# Heating_Controller.net
KiCad netlist of a schematic drawn in EAGLE
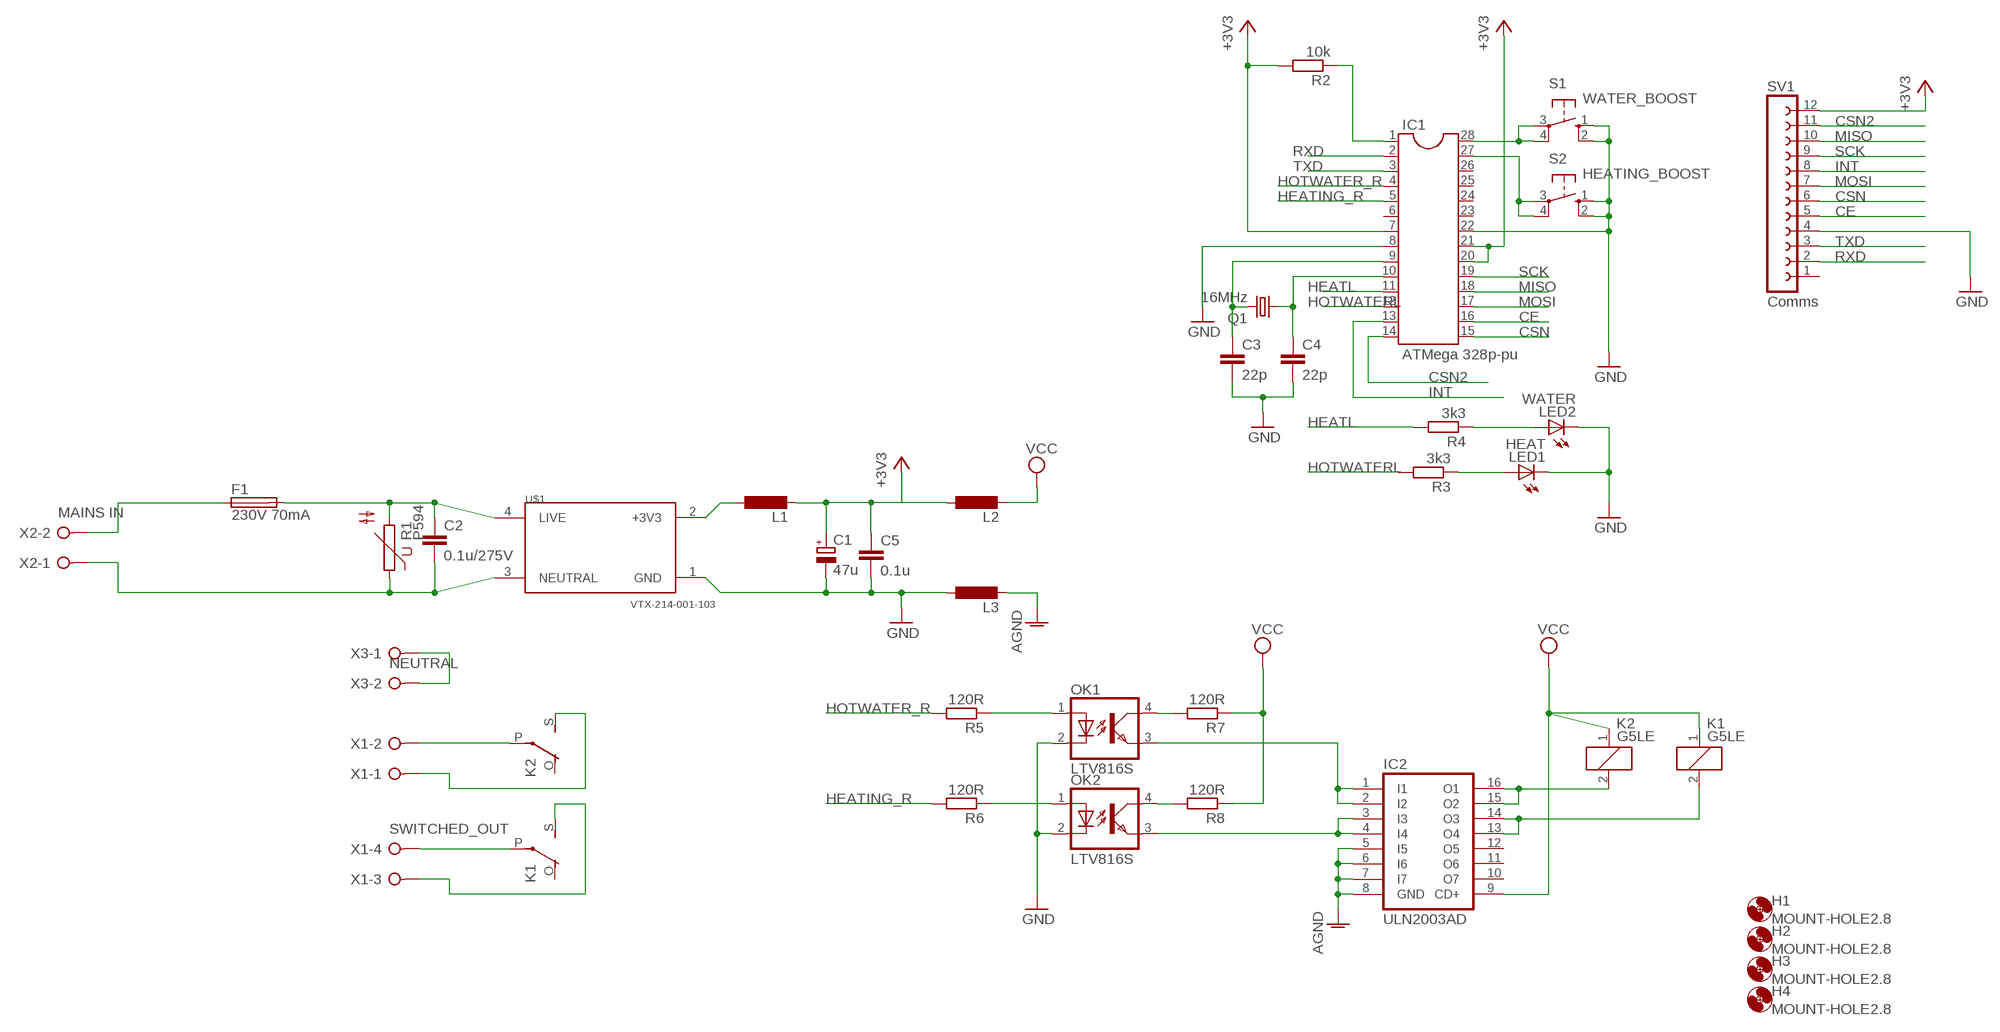
[diagram p0: schematic, sheet 1]

(export (version "E")
  (design (tool "Eeschema 10.0.6"))
  (components
    (comp (ref "C1")
      (value "47u")
      (footprint "eagle-import:E2,5-7")
      (libsource (lib "eagle-import") (part "CPOL-EUE2.5-7"))
    )
    (comp (ref "C2")
      (value "0.1u/275V")
      (footprint "eagle-import:C15B5")
      (libsource (lib "eagle-import") (part "C15/5"))
    )
    (comp (ref "C3")
      (value "22p")
      (footprint "eagle-import:C1206K")
      (libsource (lib "eagle-import") (part "C-EUC1206K"))
    )
    (comp (ref "C4")
      (value "22p")
      (footprint "eagle-import:C1206K")
      (libsource (lib "eagle-import") (part "C-EUC1206K"))
    )
    (comp (ref "C5")
      (value "0.1u")
      (footprint "eagle-import:C1206K")
      (libsource (lib "eagle-import") (part "C-EUC1206K"))
    )
    (comp (ref "F1")
      (value "230V 70mA")
      (footprint "eagle-import:SH22,5A")
      (fields (field (name "MPN") "0031.7701.11"))
      (libsource (lib "eagle-import") (part "SH22,5A"))
    )
    (comp (ref "H1")
      (value "MOUNT-HOLE2.8")
      (footprint "eagle-import:2,8")
      (libsource (lib "eagle-import") (part "MOUNT-HOLE2.8"))
    )
    (comp (ref "H2")
      (value "MOUNT-HOLE2.8")
      (footprint "eagle-import:2,8")
      (libsource (lib "eagle-import") (part "MOUNT-HOLE2.8"))
    )
    (comp (ref "H3")
      (value "MOUNT-HOLE2.8")
      (footprint "eagle-import:2,8")
      (libsource (lib "eagle-import") (part "MOUNT-HOLE2.8"))
    )
    (comp (ref "H4")
      (value "MOUNT-HOLE2.8")
      (footprint "eagle-import:2,8")
      (libsource (lib "eagle-import") (part "MOUNT-HOLE2.8"))
    )
    (comp (ref "IC1")
      (value "ATMega 328p-pu")
      (footprint "eagle-import:DIL28-3")
      (libsource (lib "eagle-import") (part "DIL28-3"))
    )
    (comp (ref "IC2")
      (value "ULN2003AD")
      (footprint "eagle-import:SO16")
      (libsource (lib "eagle-import") (part "ULN2003AD"))
    )
    (comp (ref "K1")
      (value "G5LE")
      (footprint "eagle-import:G5LE")
      (libsource (lib "eagle-import") (part "G5LE"))
    )
    (comp (ref "K2")
      (value "G5LE")
      (footprint "eagle-import:G5LE")
      (libsource (lib "eagle-import") (part "G5LE"))
    )
    (comp (ref "L1")
      (value "L-EUL3230M")
      (footprint "eagle-import:L3230M")
      (libsource (lib "eagle-import") (part "L-EUL3230M"))
    )
    (comp (ref "L2")
      (value "L-EUL3230M")
      (footprint "eagle-import:L3230M")
      (libsource (lib "eagle-import") (part "L-EUL3230M"))
    )
    (comp (ref "L3")
      (value "L-EUL3230M")
      (footprint "eagle-import:L3230M")
      (libsource (lib "eagle-import") (part "L-EUL3230M"))
    )
    (comp (ref "LED1")
      (value "HEAT")
      (footprint "eagle-import:LED5MM")
      (libsource (lib "eagle-import") (part "LED5MM"))
    )
    (comp (ref "LED2")
      (value "WATER")
      (footprint "eagle-import:LED5MM")
      (libsource (lib "eagle-import") (part "LED5MM"))
    )
    (comp (ref "OK1")
      (value "LTV816S")
      (footprint "eagle-import:DIL4-SMD")
      (libsource (lib "eagle-import") (part "LTV816S"))
    )
    (comp (ref "OK2")
      (value "LTV816S")
      (footprint "eagle-import:DIL4-SMD")
      (libsource (lib "eagle-import") (part "LTV816S"))
    )
    (comp (ref "Q1")
      (value "16MHz")
      (footprint "eagle-import:HC49_S")
      (libsource (lib "eagle-import") (part "CRYSTALHC49S"))
    )
    (comp (ref "R1")
      (value "P594")
      (footprint "eagle-import:P594")
      (libsource (lib "eagle-import") (part "P594"))
    )
    (comp (ref "R2")
      (value "10k")
      (footprint "eagle-import:R1206")
      (libsource (lib "eagle-import") (part "R-EU_R1206"))
    )
    (comp (ref "R3")
      (value "3k3")
      (footprint "eagle-import:R1206")
      (libsource (lib "eagle-import") (part "R-EU_R1206"))
    )
    (comp (ref "R4")
      (value "3k3")
      (footprint "eagle-import:R1206")
      (libsource (lib "eagle-import") (part "R-EU_R1206"))
    )
    (comp (ref "R5")
      (value "120R")
      (footprint "eagle-import:R1206")
      (libsource (lib "eagle-import") (part "R-EU_R1206"))
    )
    (comp (ref "R6")
      (value "120R")
      (footprint "eagle-import:R1206")
      (libsource (lib "eagle-import") (part "R-EU_R1206"))
    )
    (comp (ref "R7")
      (value "120R")
      (footprint "eagle-import:R1206")
      (libsource (lib "eagle-import") (part "R-EU_R1206"))
    )
    (comp (ref "R8")
      (value "120R")
      (footprint "eagle-import:R1206")
      (libsource (lib "eagle-import") (part "R-EU_R1206"))
    )
    (comp (ref "S1")
      (value "WATER_BOOST")
      (footprint "eagle-import:B3F-40XX")
      (fields (field (name "MF") "OMRON COMPONENTS USA") (field (name "MPN") "B3F-4000"))
      (libsource (lib "eagle-import") (part "40-XX"))
    )
    (comp (ref "S2")
      (value "HEATING_BOOST")
      (footprint "eagle-import:B3F-40XX")
      (fields (field (name "MF") "OMRON COMPONENTS USA") (field (name "MPN") "B3F-4000"))
      (libsource (lib "eagle-import") (part "40-XX"))
    )
    (comp (ref "SV1")
      (value "Comms")
      (footprint "eagle-import:FE12W")
      (libsource (lib "eagle-import") (part "FE12W"))
    )
    (comp (ref "U$1")
      (value "VTX-214-001-103")
      (footprint "eagle-import:VTX214001103")
      (libsource (lib "eagle-import") (part "VTX-214-001-103"))
    )
    (comp (ref "X1")
      (value "SWITCHED_OUT")
      (footprint "eagle-import:W237-4P")
      (libsource (lib "eagle-import") (part "W237-04P"))
    )
    (comp (ref "X2")
      (value "MAINS IN")
      (footprint "eagle-import:W237-132")
      (libsource (lib "eagle-import") (part "W237-02P"))
    )
    (comp (ref "X3")
      (value "NEUTRAL")
      (footprint "eagle-import:W237-132")
      (libsource (lib "eagle-import") (part "W237-02P"))
    )
  )
  (nets
    (net (code "1") (name "+3V3") (class "Default")
      (node (ref "C1") (pin "+") (pinfunction "+_+") (pintype "passive"))
      (node (ref "C5") (pin "1") (pinfunction "1_1") (pintype "passive"))
      (node (ref "IC1") (pin "20") (pinfunction "20_20") (pintype "passive"))
      (node (ref "IC1") (pin "21") (pinfunction "21_21") (pintype "passive"))
      (node (ref "IC1") (pin "7") (pinfunction "7_7") (pintype "passive"))
      (node (ref "L1") (pin "2") (pinfunction "2_2") (pintype "passive"))
      (node (ref "L2") (pin "1") (pinfunction "1_1") (pintype "passive"))
      (node (ref "R2") (pin "2") (pinfunction "2_2") (pintype "passive"))
      (node (ref "SV1") (pin "12") (pinfunction "12_12") (pintype "passive"))
    )
    (net (code "2") (name "/CE") (class "Default")
      (node (ref "IC1") (pin "16") (pinfunction "16_16") (pintype "passive"))
      (node (ref "SV1") (pin "5") (pinfunction "5_5") (pintype "passive"))
    )
    (net (code "3") (name "/CSN") (class "Default")
      (node (ref "IC1") (pin "15") (pinfunction "15_15") (pintype "passive"))
      (node (ref "SV1") (pin "6") (pinfunction "6_6") (pintype "passive"))
    )
    (net (code "4") (name "/CSN2") (class "Default")
      (node (ref "IC1") (pin "14") (pinfunction "14_14") (pintype "passive"))
      (node (ref "SV1") (pin "11") (pinfunction "11_11") (pintype "passive"))
    )
    (net (code "5") (name "/HEATING_R") (class "Default")
      (node (ref "IC1") (pin "5") (pinfunction "5_5") (pintype "passive"))
      (node (ref "R6") (pin "2") (pinfunction "2_2") (pintype "passive"))
    )
    (net (code "6") (name "/HEATL") (class "Default")
      (node (ref "IC1") (pin "11") (pinfunction "11_11") (pintype "passive"))
      (node (ref "R4") (pin "2") (pinfunction "2_2") (pintype "passive"))
    )
    (net (code "7") (name "/HOTWATERL") (class "Default")
      (node (ref "IC1") (pin "12") (pinfunction "12_12") (pintype "passive"))
      (node (ref "R3") (pin "2") (pinfunction "2_2") (pintype "passive"))
    )
    (net (code "8") (name "/HOTWATER_R") (class "Default")
      (node (ref "IC1") (pin "4") (pinfunction "4_4") (pintype "passive"))
      (node (ref "R5") (pin "2") (pinfunction "2_2") (pintype "passive"))
    )
    (net (code "9") (name "/INT") (class "Default")
      (node (ref "IC1") (pin "13") (pinfunction "13_13") (pintype "passive"))
      (node (ref "SV1") (pin "8") (pinfunction "8_8") (pintype "passive"))
    )
    (net (code "10") (name "/MISO") (class "Default")
      (node (ref "IC1") (pin "18") (pinfunction "18_18") (pintype "passive"))
      (node (ref "SV1") (pin "10") (pinfunction "10_10") (pintype "passive"))
    )
    (net (code "11") (name "/MOSI") (class "Default")
      (node (ref "IC1") (pin "17") (pinfunction "17_17") (pintype "passive"))
      (node (ref "SV1") (pin "7") (pinfunction "7_7") (pintype "passive"))
    )
    (net (code "12") (name "/RXD") (class "Default")
      (node (ref "IC1") (pin "2") (pinfunction "2_2") (pintype "passive"))
      (node (ref "SV1") (pin "2") (pinfunction "2_2") (pintype "passive"))
    )
    (net (code "13") (name "/SCK") (class "Default")
      (node (ref "IC1") (pin "19") (pinfunction "19_19") (pintype "passive"))
      (node (ref "SV1") (pin "9") (pinfunction "9_9") (pintype "passive"))
    )
    (net (code "14") (name "/TXD") (class "Default")
      (node (ref "IC1") (pin "3") (pinfunction "3_3") (pintype "passive"))
      (node (ref "SV1") (pin "3") (pinfunction "3_3") (pintype "passive"))
    )
    (net (code "15") (name "AGND") (class "Default")
      (node (ref "IC2") (pin "5") (pinfunction "I5_5") (pintype "input"))
      (node (ref "IC2") (pin "6") (pinfunction "I6_6") (pintype "input"))
      (node (ref "IC2") (pin "7") (pinfunction "I7_7") (pintype "input"))
      (node (ref "IC2") (pin "8") (pinfunction "GND_8") (pintype "power_in"))
      (node (ref "L3") (pin "2") (pinfunction "2_2") (pintype "passive"))
    )
    (net (code "16") (name "GND") (class "Default")
      (node (ref "C1") (pin "-") (pinfunction "-_-") (pintype "passive"))
      (node (ref "C3") (pin "2") (pinfunction "2_2") (pintype "passive"))
      (node (ref "C4") (pin "2") (pinfunction "2_2") (pintype "passive"))
      (node (ref "C5") (pin "2") (pinfunction "2_2") (pintype "passive"))
      (node (ref "IC1") (pin "22") (pinfunction "22_22") (pintype "passive"))
      (node (ref "IC1") (pin "8") (pinfunction "8_8") (pintype "passive"))
      (node (ref "L3") (pin "1") (pinfunction "1_1") (pintype "passive"))
      (node (ref "LED1") (pin "K") (pinfunction "C_K") (pintype "passive"))
      (node (ref "LED2") (pin "K") (pinfunction "C_K") (pintype "passive"))
      (node (ref "OK1") (pin "2") (pinfunction "C_2") (pintype "passive"))
      (node (ref "OK2") (pin "2") (pinfunction "C_2") (pintype "passive"))
      (node (ref "S1") (pin "1") (pinfunction "S_1") (pintype "passive"))
      (node (ref "S1") (pin "2") (pinfunction "S1_2") (pintype "passive"))
      (node (ref "S2") (pin "1") (pinfunction "S_1") (pintype "passive"))
      (node (ref "S2") (pin "2") (pinfunction "S1_2") (pintype "passive"))
      (node (ref "SV1") (pin "4") (pinfunction "4_4") (pintype "passive"))
      (node (ref "U$1") (pin "1") (pinfunction "GND_1") (pintype "power_in"))
    )
    (net (code "17") (name "Net-(C3-Pad1)") (class "Default")
      (node (ref "C3") (pin "1") (pinfunction "1_1") (pintype "passive"))
      (node (ref "IC1") (pin "9") (pinfunction "9_9") (pintype "passive"))
      (node (ref "Q1") (pin "2") (pinfunction "2_2") (pintype "passive"))
    )
    (net (code "18") (name "Net-(C4-Pad1)") (class "Default")
      (node (ref "C4") (pin "1") (pinfunction "1_1") (pintype "passive"))
      (node (ref "IC1") (pin "10") (pinfunction "10_10") (pintype "passive"))
      (node (ref "Q1") (pin "1") (pinfunction "1_1") (pintype "passive"))
    )
    (net (code "19") (name "Net-(IC1-Pad1)") (class "Default")
      (node (ref "IC1") (pin "1") (pinfunction "1_1") (pintype "passive"))
      (node (ref "R2") (pin "1") (pinfunction "1_1") (pintype "passive"))
    )
    (net (code "20") (name "Net-(IC2-I1)") (class "Default")
      (node (ref "IC2") (pin "1") (pinfunction "I1_1") (pintype "input"))
      (node (ref "IC2") (pin "2") (pinfunction "I2_2") (pintype "input"))
      (node (ref "OK1") (pin "3") (pinfunction "EMIT_3") (pintype "passive"))
    )
    (net (code "21") (name "Net-(IC2-I3)") (class "Default")
      (node (ref "IC2") (pin "3") (pinfunction "I3_3") (pintype "input"))
      (node (ref "IC2") (pin "4") (pinfunction "I4_4") (pintype "input"))
      (node (ref "OK2") (pin "3") (pinfunction "EMIT_3") (pintype "passive"))
    )
    (net (code "22") (name "Net-(IC2-O1)") (class "Default")
      (node (ref "IC2") (pin "15") (pinfunction "O2_15") (pintype "open_collector"))
      (node (ref "IC2") (pin "16") (pinfunction "O1_16") (pintype "open_collector"))
      (node (ref "K2") (pin "2") (pinfunction "2_2") (pintype "passive"))
    )
    (net (code "23") (name "Net-(IC2-O3)") (class "Default")
      (node (ref "IC2") (pin "13") (pinfunction "O4_13") (pintype "open_collector"))
      (node (ref "IC2") (pin "14") (pinfunction "O3_14") (pintype "open_collector"))
      (node (ref "K1") (pin "2") (pinfunction "2_2") (pintype "passive"))
    )
    (net (code "24") (name "Net-(LED1-PadA)") (class "Default")
      (node (ref "LED1") (pin "A") (pinfunction "A_A") (pintype "passive"))
      (node (ref "R3") (pin "1") (pinfunction "1_1") (pintype "passive"))
    )
    (net (code "25") (name "Net-(LED2-PadA)") (class "Default")
      (node (ref "LED2") (pin "A") (pinfunction "A_A") (pintype "passive"))
      (node (ref "R4") (pin "1") (pinfunction "1_1") (pintype "passive"))
    )
    (net (code "26") (name "Net-(OK1-A)") (class "Default")
      (node (ref "OK1") (pin "1") (pinfunction "A_1") (pintype "passive"))
      (node (ref "R5") (pin "1") (pinfunction "1_1") (pintype "passive"))
    )
    (net (code "27") (name "Net-(OK1-COL)") (class "Default")
      (node (ref "OK1") (pin "4") (pinfunction "COL_4") (pintype "passive"))
      (node (ref "R7") (pin "2") (pinfunction "2_2") (pintype "passive"))
    )
    (net (code "28") (name "Net-(OK2-A)") (class "Default")
      (node (ref "OK2") (pin "1") (pinfunction "A_1") (pintype "passive"))
      (node (ref "R6") (pin "1") (pinfunction "1_1") (pintype "passive"))
    )
    (net (code "29") (name "Net-(OK2-COL)") (class "Default")
      (node (ref "OK2") (pin "4") (pinfunction "COL_4") (pintype "passive"))
      (node (ref "R8") (pin "2") (pinfunction "2_2") (pintype "passive"))
    )
    (net (code "30") (name "Net-(S1-P)") (class "Default")
      (node (ref "IC1") (pin "28") (pinfunction "28_28") (pintype "passive"))
      (node (ref "S1") (pin "3") (pinfunction "P_3") (pintype "passive"))
      (node (ref "S1") (pin "4") (pinfunction "P1_4") (pintype "passive"))
    )
    (net (code "31") (name "Net-(S2-P)") (class "Default")
      (node (ref "IC1") (pin "27") (pinfunction "27_27") (pintype "passive"))
      (node (ref "S2") (pin "3") (pinfunction "P_3") (pintype "passive"))
      (node (ref "S2") (pin "4") (pinfunction "P1_4") (pintype "passive"))
    )
    (net (code "32") (name "Net-(U$1-+3V3)") (class "Default")
      (node (ref "L1") (pin "1") (pinfunction "1_1") (pintype "passive"))
      (node (ref "U$1") (pin "2") (pinfunction "+3V3_2") (pintype "power_in"))
    )
    (net (code "33") (name "Net-(U$1-LIVE)") (class "Default")
      (node (ref "C2") (pin "1") (pinfunction "1_1") (pintype "passive"))
      (node (ref "F1") (pin "2") (pinfunction "2_2") (pintype "passive"))
      (node (ref "R1") (pin "2") (pinfunction "2_2") (pintype "passive"))
      (node (ref "U$1") (pin "4") (pinfunction "LIVE_4") (pintype "input"))
    )
    (net (code "34") (name "Net-(U$1-NEUTRAL)") (class "Default")
      (node (ref "C2") (pin "2") (pinfunction "2_2") (pintype "passive"))
      (node (ref "R1") (pin "1") (pinfunction "1_1") (pintype "passive"))
      (node (ref "U$1") (pin "3") (pinfunction "NEUTRAL_3") (pintype "input"))
      (node (ref "X2") (pin "1") (pinfunction "KL_1") (pintype "passive"))
    )
    (net (code "35") (name "Net-(X1A-KL)") (class "Default")
      (node (ref "K2") (pin "S") (pinfunction "S_S") (pintype "passive"))
      (node (ref "X1") (pin "1") (pinfunction "KL_1") (pintype "passive"))
    )
    (net (code "36") (name "Net-(X1B-KL)") (class "Default")
      (node (ref "K2") (pin "P") (pinfunction "P_P") (pintype "passive"))
      (node (ref "X1") (pin "2") (pinfunction "KL_2") (pintype "passive"))
    )
    (net (code "37") (name "Net-(X1C-KL)") (class "Default")
      (node (ref "K1") (pin "S") (pinfunction "S_S") (pintype "passive"))
      (node (ref "X1") (pin "3") (pinfunction "KL_3") (pintype "passive"))
    )
    (net (code "38") (name "Net-(X1D-KL)") (class "Default")
      (node (ref "K1") (pin "P") (pinfunction "P_P") (pintype "passive"))
      (node (ref "X1") (pin "4") (pinfunction "KL_4") (pintype "passive"))
    )
    (net (code "39") (name "Net-(X2B-KL)") (class "Default")
      (node (ref "F1") (pin "1") (pinfunction "1_1") (pintype "passive"))
      (node (ref "X2") (pin "2") (pinfunction "KL_2") (pintype "passive"))
    )
    (net (code "40") (name "Net-(X3A-KL)") (class "Default")
      (node (ref "X3") (pin "1") (pinfunction "KL_1") (pintype "passive"))
      (node (ref "X3") (pin "2") (pinfunction "KL_2") (pintype "passive"))
    )
    (net (code "41") (name "VCC") (class "Default")
      (node (ref "IC2") (pin "9") (pinfunction "CD+_9") (pintype "passive"))
      (node (ref "K1") (pin "1") (pinfunction "1_1") (pintype "passive"))
      (node (ref "K2") (pin "1") (pinfunction "1_1") (pintype "passive"))
      (node (ref "L2") (pin "2") (pinfunction "2_2") (pintype "passive"))
      (node (ref "R7") (pin "1") (pinfunction "1_1") (pintype "passive"))
      (node (ref "R8") (pin "1") (pinfunction "1_1") (pintype "passive"))
    )
    (net (code "42") (name "unconnected-(IC1-Pad6)") (class "Default")
      (node (ref "IC1") (pin "6") (pinfunction "6_6") (pintype "passive"))
    )
    (net (code "43") (name "unconnected-(IC1-Pad23)") (class "Default")
      (node (ref "IC1") (pin "23") (pinfunction "23_23") (pintype "passive"))
    )
    (net (code "44") (name "unconnected-(IC1-Pad24)") (class "Default")
      (node (ref "IC1") (pin "24") (pinfunction "24_24") (pintype "passive"))
    )
    (net (code "45") (name "unconnected-(IC1-Pad25)") (class "Default")
      (node (ref "IC1") (pin "25") (pinfunction "25_25") (pintype "passive"))
    )
    (net (code "46") (name "unconnected-(IC1-Pad26)") (class "Default")
      (node (ref "IC1") (pin "26") (pinfunction "26_26") (pintype "passive"))
    )
    (net (code "47") (name "unconnected-(IC2-O5-Pad12)") (class "Default")
      (node (ref "IC2") (pin "12") (pinfunction "O5_12") (pintype "open_collector"))
    )
    (net (code "48") (name "unconnected-(IC2-O6-Pad11)") (class "Default")
      (node (ref "IC2") (pin "11") (pinfunction "O6_11") (pintype "open_collector"))
    )
    (net (code "49") (name "unconnected-(IC2-O7-Pad10)") (class "Default")
      (node (ref "IC2") (pin "10") (pinfunction "O7_10") (pintype "open_collector"))
    )
    (net (code "50") (name "unconnected-(K1-PadO)") (class "Default")
      (node (ref "K1") (pin "O") (pinfunction "O_O") (pintype "passive"))
    )
    (net (code "51") (name "unconnected-(K2-PadO)") (class "Default")
      (node (ref "K2") (pin "O") (pinfunction "O_O") (pintype "passive"))
    )
    (net (code "52") (name "unconnected-(SV1-Pad1)") (class "Default")
      (node (ref "SV1") (pin "1") (pinfunction "1_1") (pintype "passive"))
    )
  )
)
